# 11-SoC_POWER1.net
KiCad netlist of a schematic drawn in Altium Designer
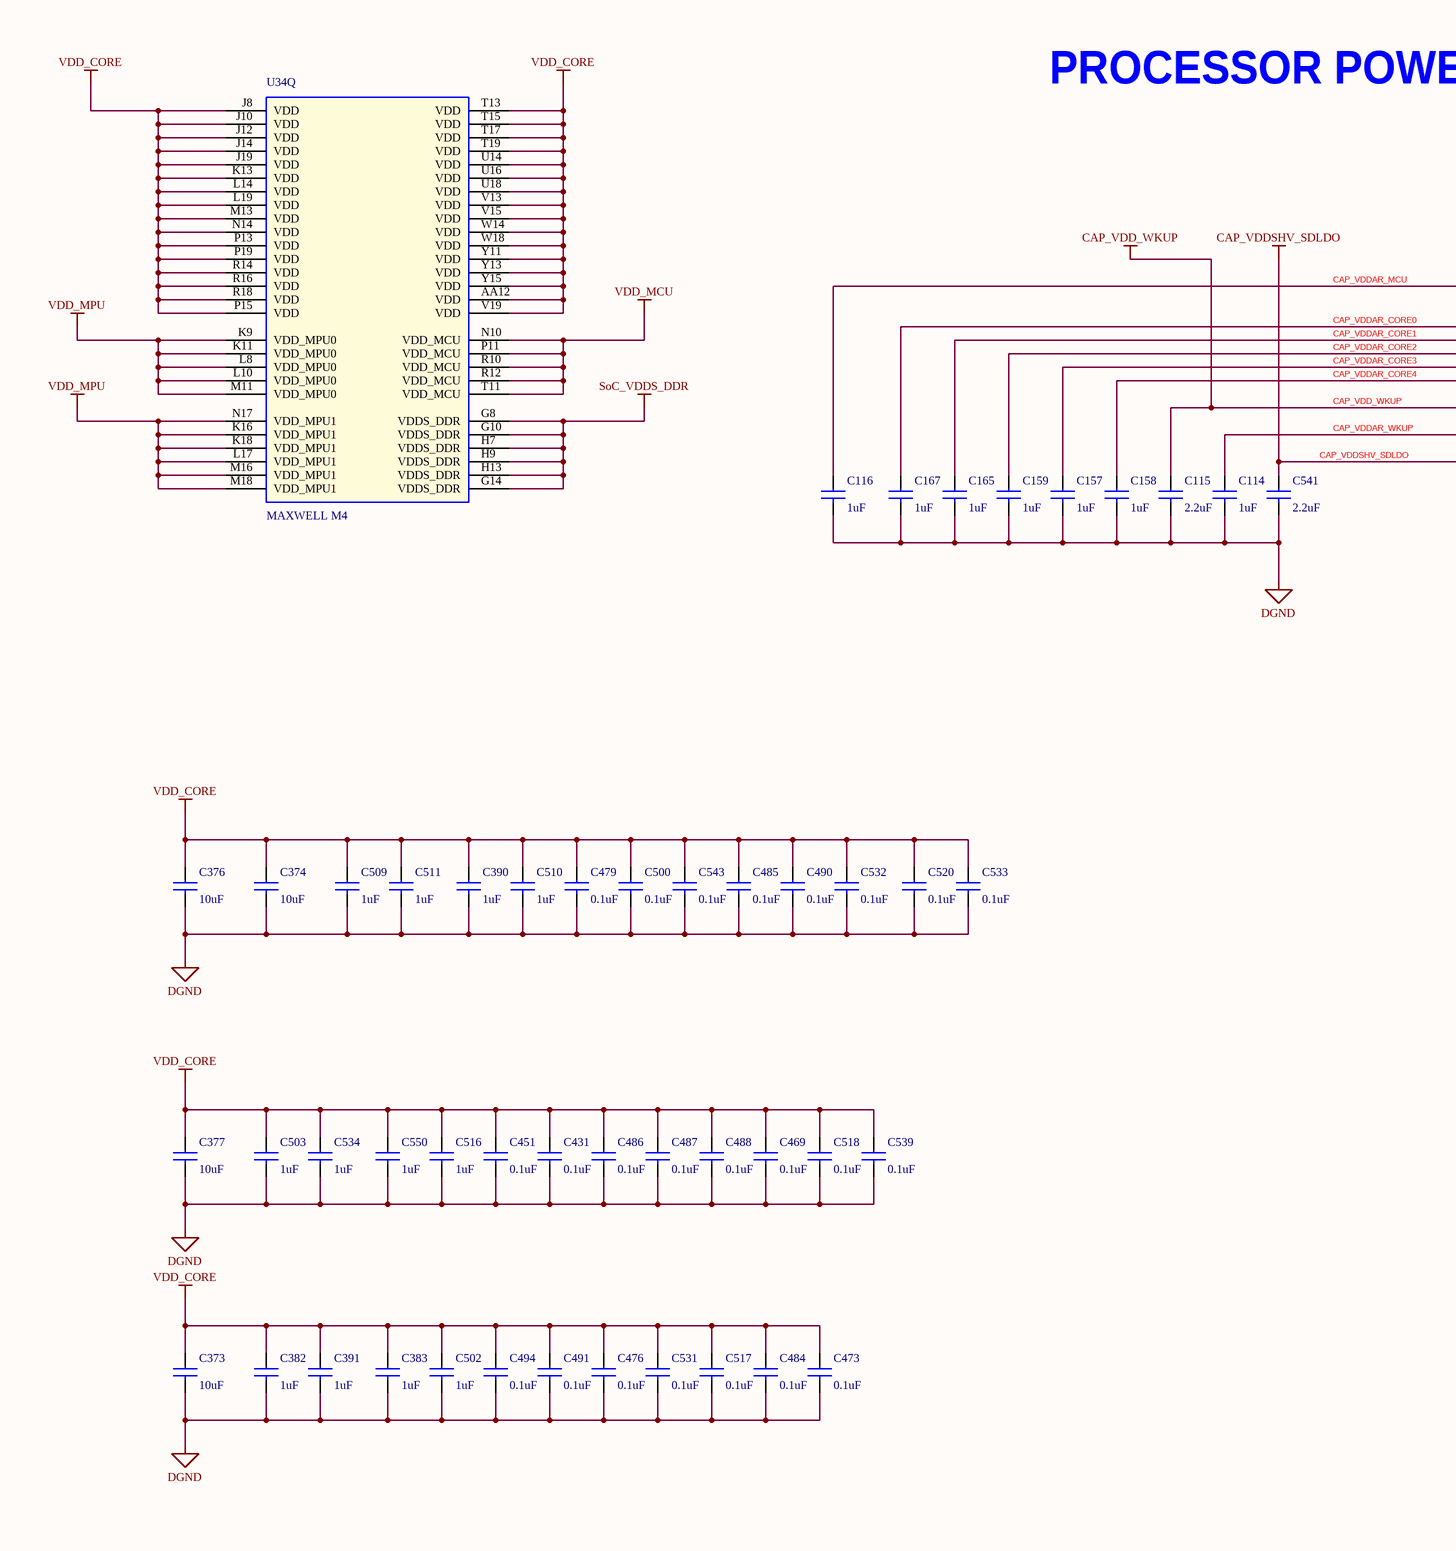
[diagram p0: 11-SoC POWER1.SchDoc, left]
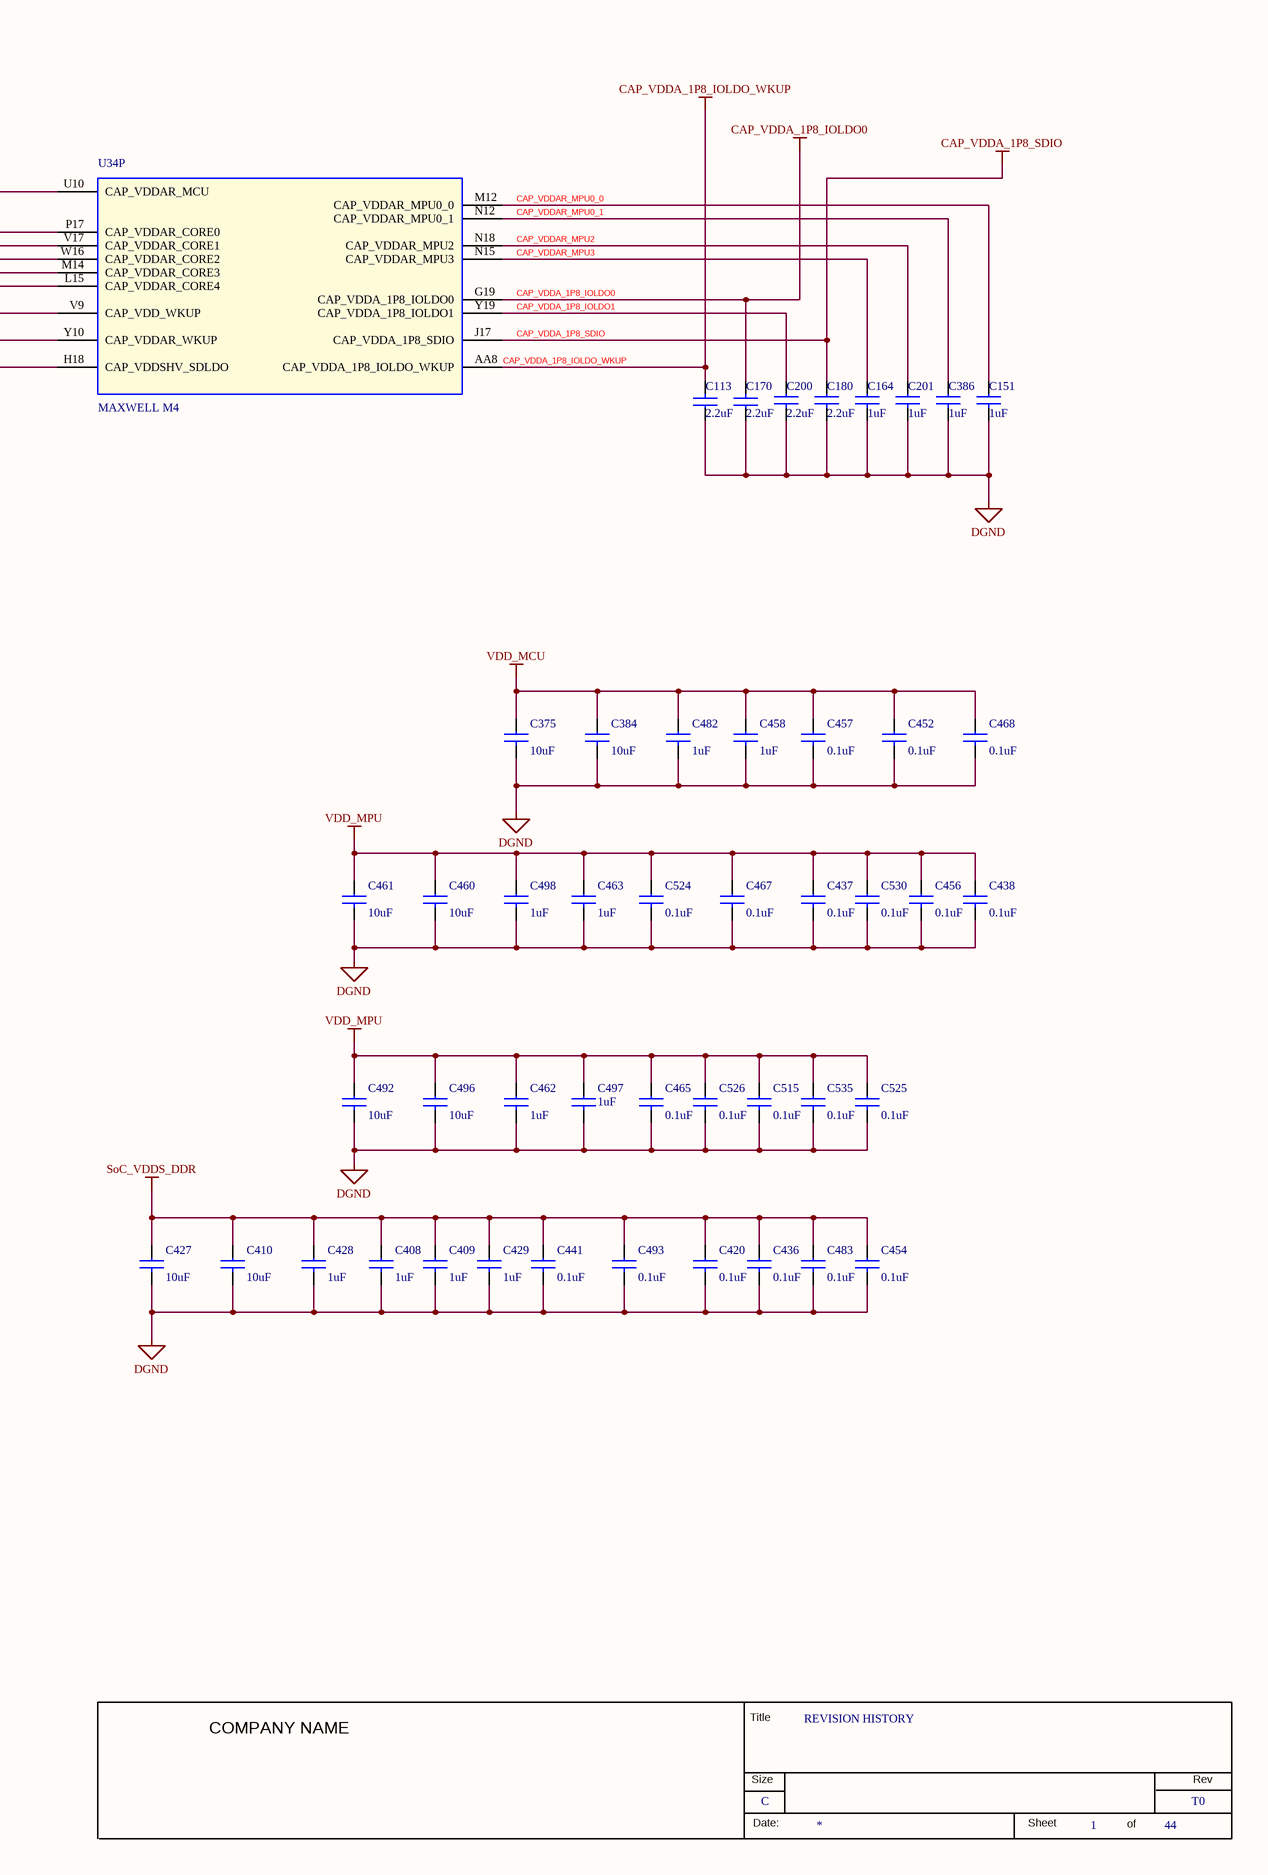
[diagram p1: 11-SoC POWER1.SchDoc, right]

(export (version "E")
  (design (tool "Eeschema 10.0.6"))
  (components
    (comp (ref "C113")
      (value "2.2uF")
      (footprint "CAP0603")
      (description "CAP CERAMIC 2.2uF 10V 10% X5R 0603")
      (fields
        (field (name "MISTRAL PART NO") "120009030289-R")
        (field (name "MFR_PART_NUMBER") "C0603C225K8PACTU")
      )
      (libsource (lib "*") (part "CAP_Dup5"))
    )
    (comp (ref "C114")
      (value "1uF")
      (footprint "CAP0402_0-75")
      (description "CAP CERAMIC 1uF 16V 20% X5R 0402")
      (fields (field (name "DISTRIBUTOR_PART_NUMBER") "587-5514-1-ND") (field (name "VOLTAGE") "16V"))
      (libsource (lib "*") (part "CAP_Dup5"))
    )
    (comp (ref "C115")
      (value "2.2uF")
      (footprint "CAP0402_0-75")
      (description "CAP CERAMIC 2.2uF 10V 20% X5R 0402")
      (fields
        (field (name "MISTRAL PART NO") "120018010016-R")
        (field (name "MFR_PART_NUMBER") "GRT155R61A225ME01D")
      )
      (libsource (lib "*") (part "CAP_Dup5"))
    )
    (comp (ref "C116")
      (value "1uF")
      (footprint "CAP0402_0-75")
      (description "CAP CERAMIC 1uF 16V 20% X5R 0402")
      (fields
        (field (name "MISTRAL PART NO") "120018020006-R")
        (field (name "MFR_PART_NUMBER") "EMK105BJ105MV-F")
      )
      (libsource (lib "*") (part "CAP_Dup5"))
    )
    (comp (ref "C151")
      (value "1uF")
      (footprint "CAP0402_0-75")
      (description "CAP CERAMIC 1uF 16V 20% X5R 0402")
      (fields (field (name "DISTRIBUTOR_PART_NUMBER") "587-5514-1-ND") (field (name "VOLTAGE") "16V"))
      (libsource (lib "*") (part "CAP_Dup5"))
    )
    (comp (ref "C157")
      (value "1uF")
      (footprint "CAP0402_0-75")
      (description "CAP CERAMIC 1uF 16V 20% X5R 0402")
      (fields (field (name "DISTRIBUTOR_PART_NUMBER") "587-5514-1-ND") (field (name "VOLTAGE") "16V"))
      (libsource (lib "*") (part "CAP_Dup5"))
    )
    (comp (ref "C158")
      (value "1uF")
      (footprint "CAP0402_0-75")
      (description "CAP CERAMIC 1uF 16V 20% X5R 0402")
      (fields
        (field (name "MISTRAL PART NO") "120018020006-R")
        (field (name "MFR_PART_NUMBER") "EMK105BJ105MV-F")
      )
      (libsource (lib "*") (part "CAP_Dup5"))
    )
    (comp (ref "C159")
      (value "1uF")
      (footprint "CAP0402_0-75")
      (description "CAP CERAMIC 1uF 16V 20% X5R 0402")
      (fields (field (name "DISTRIBUTOR_PART_NUMBER") "587-5514-1-ND") (field (name "VOLTAGE") "16V"))
      (libsource (lib "*") (part "CAP_Dup5"))
    )
    (comp (ref "C164")
      (value "1uF")
      (footprint "CAP0402_0-75")
      (description "CAP CERAMIC 1uF 16V 20% X5R 0402")
      (fields (field (name "DISTRIBUTOR_PART_NUMBER") "587-5514-1-ND") (field (name "VOLTAGE") "16V"))
      (libsource (lib "*") (part "CAP_Dup5"))
    )
    (comp (ref "C165")
      (value "1uF")
      (footprint "CAP0402_0-75")
      (description "CAP CERAMIC 1uF 16V 20% X5R 0402")
      (fields (field (name "DISTRIBUTOR_PART_NUMBER") "587-5514-1-ND") (field (name "VOLTAGE") "16V"))
      (libsource (lib "*") (part "CAP_Dup5"))
    )
    (comp (ref "C167")
      (value "1uF")
      (footprint "CAP0402_0-75")
      (description "CAP CERAMIC 1uF 16V 20% X5R 0402")
      (fields
        (field (name "MISTRAL PART NO") "120018020006-R")
        (field (name "MFR_PART_NUMBER") "EMK105BJ105MV-F")
      )
      (libsource (lib "*") (part "CAP_Dup5"))
    )
    (comp (ref "C170")
      (value "2.2uF")
      (footprint "CAP0603")
      (description "CAP CERAMIC 2.2uF 10V 10% X5R 0603")
      (fields
        (field (name "MISTRAL PART NO") "120009030289-R")
        (field (name "MFR_PART_NUMBER") "C0603C225K8PACTU")
      )
      (libsource (lib "*") (part "CAP_Dup5"))
    )
    (comp (ref "C180")
      (value "2.2uF")
      (footprint "CAP0402_0-75")
      (description "CAP CERAMIC 2.2uF 10V 20% X5R 0402")
      (fields
        (field (name "MISTRAL PART NO") "120018010016-R")
        (field (name "MFR_PART_NUMBER") "GRT155R61A225ME01D")
      )
      (libsource (lib "*") (part "CAP_Dup5"))
    )
    (comp (ref "C200")
      (value "2.2uF")
      (footprint "CAP0402_0-75")
      (description "CAP CERAMIC 2.2uF 10V 20% X5R 0402")
      (fields
        (field (name "MISTRAL PART NO") "120018010016-R")
        (field (name "MFR_PART_NUMBER") "GRT155R61A225ME01D")
      )
      (libsource (lib "*") (part "CAP_Dup5"))
    )
    (comp (ref "C201")
      (value "1uF")
      (footprint "CAP0402_0-75")
      (description "CAP CERAMIC 1uF 16V 20% X5R 0402")
      (fields
        (field (name "MISTRAL PART NO") "120018020006-R")
        (field (name "MFR_PART_NUMBER") "EMK105BJ105MV-F")
      )
      (libsource (lib "*") (part "CAP_Dup5"))
    )
    (comp (ref "C373")
      (value "10uF")
      (footprint "CAP0603_1")
      (description "CAP CERAMIC 10uF 10V 10% X5R 0603")
      (fields (field (name "DISTRIBUTOR_PART_NUMBER") "478-10766-1-ND") (field (name "VOLTAGE") "10V"))
      (libsource (lib "*") (part "CAP_Dup5"))
    )
    (comp (ref "C374")
      (value "10uF")
      (footprint "CAP0603_1")
      (description "CAP CERAMIC 10uF 10V 10% X5R 0603")
      (fields (field (name "DISTRIBUTOR_PART_NUMBER") "478-10766-1-ND") (field (name "VOLTAGE") "10V"))
      (libsource (lib "*") (part "CAP_Dup5"))
    )
    (comp (ref "C375")
      (value "10uF")
      (footprint "CAP0603_1")
      (description "CAP CERAMIC 10uF 10V 10% X5R 0603")
      (fields
        (field (name "MISTRAL PART NO") "120010080001-R")
        (field (name "MFR_PART_NUMBER") "0603ZD106KAT2A")
      )
      (libsource (lib "*") (part "CAP_Dup5"))
    )
    (comp (ref "C376")
      (value "10uF")
      (footprint "CAP0603_1")
      (description "CAP CERAMIC 10uF 10V 10% X5R 0603")
      (fields (field (name "DISTRIBUTOR_PART_NUMBER") "478-10766-1-ND") (field (name "VOLTAGE") "10V"))
      (libsource (lib "*") (part "CAP_Dup5"))
    )
    (comp (ref "C377")
      (value "10uF")
      (footprint "CAP0603_1")
      (description "CAP CERAMIC 10uF 10V 10% X5R 0603")
      (fields
        (field (name "MISTRAL PART NO") "120010080001-R")
        (field (name "MFR_PART_NUMBER") "0603ZD106KAT2A")
      )
      (libsource (lib "*") (part "CAP_Dup5"))
    )
    (comp (ref "C382")
      (value "1uF")
      (footprint "CAP0402_0-75")
      (description "CAP CERAMIC 1uF 16V 20% X5R 0402")
      (fields (field (name "DISTRIBUTOR_PART_NUMBER") "587-5514-1-ND") (field (name "VOLTAGE") "16V"))
      (libsource (lib "*") (part "CAP_Dup5"))
    )
    (comp (ref "C383")
      (value "1uF")
      (footprint "CAP0402_0-75")
      (description "CAP CERAMIC 1uF 16V 20% X5R 0402")
      (fields (field (name "DISTRIBUTOR_PART_NUMBER") "587-5514-1-ND") (field (name "VOLTAGE") "16V"))
      (libsource (lib "*") (part "CAP_Dup5"))
    )
    (comp (ref "C384")
      (value "10uF")
      (footprint "CAP0603_1")
      (description "CAP CERAMIC 10uF 10V 10% X5R 0603")
      (fields
        (field (name "MISTRAL PART NO") "120010080001-R")
        (field (name "MFR_PART_NUMBER") "0603ZD106KAT2A")
      )
      (libsource (lib "*") (part "CAP_Dup5"))
    )
    (comp (ref "C386")
      (value "1uF")
      (footprint "CAP0402_0-75")
      (description "CAP CERAMIC 1uF 16V 20% X5R 0402")
      (fields (field (name "DISTRIBUTOR_PART_NUMBER") "587-5514-1-ND") (field (name "VOLTAGE") "16V"))
      (libsource (lib "*") (part "CAP_Dup5"))
    )
    (comp (ref "C390")
      (value "1uF")
      (footprint "CAP0402_0-75")
      (description "CAP CERAMIC 1uF 16V 20% X5R 0402")
      (fields (field (name "DISTRIBUTOR_PART_NUMBER") "587-5514-1-ND") (field (name "VOLTAGE") "16V"))
      (libsource (lib "*") (part "CAP_Dup5"))
    )
    (comp (ref "C391")
      (value "1uF")
      (footprint "CAP0402_0-75")
      (description "CAP CERAMIC 1uF 16V 20% X5R 0402")
      (fields (field (name "DISTRIBUTOR_PART_NUMBER") "587-5514-1-ND") (field (name "VOLTAGE") "16V"))
      (libsource (lib "*") (part "CAP_Dup5"))
    )
    (comp (ref "C408")
      (value "1uF")
      (footprint "CAP0402_0-75")
      (description "CAP CERAMIC 1uF 16V 20% X5R 0402")
      (fields (field (name "DISTRIBUTOR_PART_NUMBER") "587-5514-1-ND") (field (name "VOLTAGE") "16V"))
      (libsource (lib "*") (part "CAP_Dup5"))
    )
    (comp (ref "C409")
      (value "1uF")
      (footprint "CAP0402_0-75")
      (description "CAP CERAMIC 1uF 16V 20% X5R 0402")
      (fields (field (name "DISTRIBUTOR_PART_NUMBER") "587-5514-1-ND") (field (name "VOLTAGE") "16V"))
      (libsource (lib "*") (part "CAP_Dup5"))
    )
    (comp (ref "C410")
      (value "10uF")
      (footprint "CAP0603_1")
      (description "CAP CERAMIC 10uF 10V 10% X5R 0603")
      (fields
        (field (name "MISTRAL PART NO") "120010080001-R")
        (field (name "MFR_PART_NUMBER") "0603ZD106KAT2A")
      )
      (libsource (lib "*") (part "CAP_Dup5"))
    )
    (comp (ref "C420")
      (value "0.1uF")
      (footprint "CAP0201_0-5")
      (description "CAP CERAMIC 0.1uF 16V 10% X5R 0201")
      (fields
        (field (name "MISTRAL PART NO") "120009030072-R")
        (field (name "MFR_PART_NUMBER") "GRM033R61C104KE84J")
      )
      (libsource (lib "*") (part "CAP_Dup5"))
    )
    (comp (ref "C427")
      (value "10uF")
      (footprint "CAP0603_1")
      (description "CAP CERAMIC 10uF 10V 10% X5R 0603")
      (fields
        (field (name "MISTRAL PART NO") "120010080001-R")
        (field (name "MFR_PART_NUMBER") "0603ZD106KAT2A")
      )
      (libsource (lib "*") (part "CAP_Dup5"))
    )
    (comp (ref "C428")
      (value "1uF")
      (footprint "CAP0402_0-75")
      (description "CAP CERAMIC 1uF 16V 20% X5R 0402")
      (fields
        (field (name "MISTRAL PART NO") "120018020006-R")
        (field (name "MFR_PART_NUMBER") "EMK105BJ105MV-F")
      )
      (libsource (lib "*") (part "CAP_Dup5"))
    )
    (comp (ref "C429")
      (value "1uF")
      (footprint "CAP0402_0-75")
      (description "CAP CERAMIC 1uF 16V 20% X5R 0402")
      (fields
        (field (name "MISTRAL PART NO") "120018020006-R")
        (field (name "MFR_PART_NUMBER") "EMK105BJ105MV-F")
      )
      (libsource (lib "*") (part "CAP_Dup5"))
    )
    (comp (ref "C431")
      (value "0.1uF")
      (footprint "CAP0201_0-5")
      (description "CAP CERAMIC 0.1uF 16V 10% X5R 0201")
      (fields (field (name "DISTRIBUTOR_PART_NUMBER") "490-16742-1-ND") (field (name "VOLTAGE") "16V"))
      (libsource (lib "*") (part "CAP_Dup5"))
    )
    (comp (ref "C436")
      (value "0.1uF")
      (footprint "CAP0201_0-5")
      (description "CAP CERAMIC 0.1uF 16V 10% X5R 0201")
      (fields (field (name "DISTRIBUTOR_PART_NUMBER") "490-16742-1-ND") (field (name "VOLTAGE") "16V"))
      (libsource (lib "*") (part "CAP_Dup5"))
    )
    (comp (ref "C437")
      (value "0.1uF")
      (footprint "CAP0201_0-5")
      (description "CAP CERAMIC 0.1uF 16V 10% X5R 0201")
      (fields
        (field (name "MISTRAL PART NO") "120009030072-R")
        (field (name "MFR_PART_NUMBER") "GRM033R61C104KE84J")
      )
      (libsource (lib "*") (part "CAP_Dup5"))
    )
    (comp (ref "C438")
      (value "0.1uF")
      (footprint "CAP0201_0-5")
      (description "CAP CERAMIC 0.1uF 16V 10% X5R 0201")
      (fields (field (name "DISTRIBUTOR_PART_NUMBER") "490-16742-1-ND") (field (name "VOLTAGE") "16V"))
      (libsource (lib "*") (part "CAP_Dup5"))
    )
    (comp (ref "C441")
      (value "0.1uF")
      (footprint "CAP0201_0-5")
      (description "CAP CERAMIC 0.1uF 16V 10% X5R 0201")
      (fields
        (field (name "MISTRAL PART NO") "120009030072-R")
        (field (name "MFR_PART_NUMBER") "GRM033R61C104KE84J")
      )
      (libsource (lib "*") (part "CAP_Dup5"))
    )
    (comp (ref "C451")
      (value "0.1uF")
      (footprint "CAP0201_0-5")
      (description "CAP CERAMIC 0.1uF 16V 10% X5R 0201")
      (fields (field (name "DISTRIBUTOR_PART_NUMBER") "490-16742-1-ND") (field (name "VOLTAGE") "16V"))
      (libsource (lib "*") (part "CAP_Dup5"))
    )
    (comp (ref "C452")
      (value "0.1uF")
      (footprint "CAP0201_0-5")
      (description "CAP CERAMIC 0.1uF 16V 10% X5R 0201")
      (fields
        (field (name "MISTRAL PART NO") "120009030072-R")
        (field (name "MFR_PART_NUMBER") "GRM033R61C104KE84J")
      )
      (libsource (lib "*") (part "CAP_Dup5"))
    )
    (comp (ref "C454")
      (value "0.1uF")
      (footprint "CAP0201_0-5")
      (description "CAP CERAMIC 0.1uF 16V 10% X5R 0201")
      (fields
        (field (name "MISTRAL PART NO") "120009030072-R")
        (field (name "MFR_PART_NUMBER") "GRM033R61C104KE84J")
      )
      (libsource (lib "*") (part "CAP_Dup5"))
    )
    (comp (ref "C456")
      (value "0.1uF")
      (footprint "CAP0201_0-5")
      (description "CAP CERAMIC 0.1uF 16V 10% X5R 0201")
      (fields
        (field (name "MISTRAL PART NO") "120009030072-R")
        (field (name "MFR_PART_NUMBER") "GRM033R61C104KE84J")
      )
      (libsource (lib "*") (part "CAP_Dup5"))
    )
    (comp (ref "C457")
      (value "0.1uF")
      (footprint "CAP0201_0-5")
      (description "CAP CERAMIC 0.1uF 16V 10% X5R 0201")
      (fields (field (name "DISTRIBUTOR_PART_NUMBER") "490-16742-1-ND") (field (name "VOLTAGE") "16V"))
      (libsource (lib "*") (part "CAP_Dup5"))
    )
    (comp (ref "C458")
      (value "1uF")
      (footprint "CAP0402_0-75")
      (description "CAP CERAMIC 1uF 16V 20% X5R 0402")
      (fields (field (name "DISTRIBUTOR_PART_NUMBER") "587-5514-1-ND") (field (name "VOLTAGE") "16V"))
      (libsource (lib "*") (part "CAP_Dup5"))
    )
    (comp (ref "C460")
      (value "10uF")
      (footprint "CAP0603_1")
      (description "CAP CERAMIC 10uF 10V 10% X5R 0603")
      (fields (field (name "DISTRIBUTOR_PART_NUMBER") "478-10766-1-ND") (field (name "VOLTAGE") "10V"))
      (libsource (lib "*") (part "CAP_Dup5"))
    )
    (comp (ref "C461")
      (value "10uF")
      (footprint "CAP0603_1")
      (description "CAP CERAMIC 10uF 10V 10% X5R 0603")
      (fields (field (name "DISTRIBUTOR_PART_NUMBER") "478-10766-1-ND") (field (name "VOLTAGE") "10V"))
      (libsource (lib "*") (part "CAP_Dup5"))
    )
    (comp (ref "C462")
      (value "1uF")
      (footprint "CAP0402_0-75")
      (description "CAP CERAMIC 1uF 16V 20% X5R 0402")
      (fields
        (field (name "MISTRAL PART NO") "120018020006-R")
        (field (name "MFR_PART_NUMBER") "EMK105BJ105MV-F")
      )
      (libsource (lib "*") (part "CAP_Dup5"))
    )
    (comp (ref "C463")
      (value "1uF")
      (footprint "CAP0402_0-75")
      (description "CAP CERAMIC 1uF 16V 20% X5R 0402")
      (fields
        (field (name "MISTRAL PART NO") "120018020006-R")
        (field (name "MFR_PART_NUMBER") "EMK105BJ105MV-F")
      )
      (libsource (lib "*") (part "CAP_Dup5"))
    )
    (comp (ref "C465")
      (value "0.1uF")
      (footprint "CAP0201_0-5")
      (description "CAP CERAMIC 0.1uF 16V 10% X5R 0201")
      (fields
        (field (name "MISTRAL PART NO") "120009030072-R")
        (field (name "MFR_PART_NUMBER") "GRM033R61C104KE84J")
      )
      (libsource (lib "*") (part "CAP_Dup5"))
    )
    (comp (ref "C467")
      (value "0.1uF")
      (footprint "CAP0201_0-5")
      (description "CAP CERAMIC 0.1uF 16V 10% X5R 0201")
      (fields (field (name "DISTRIBUTOR_PART_NUMBER") "490-16742-1-ND") (field (name "VOLTAGE") "16V"))
      (libsource (lib "*") (part "CAP_Dup5"))
    )
    (comp (ref "C468")
      (value "0.1uF")
      (footprint "CAP0201_0-5")
      (description "CAP CERAMIC 0.1uF 16V 10% X5R 0201")
      (fields (field (name "DISTRIBUTOR_PART_NUMBER") "490-16742-1-ND") (field (name "VOLTAGE") "16V"))
      (libsource (lib "*") (part "CAP_Dup5"))
    )
    (comp (ref "C469")
      (value "0.1uF")
      (footprint "CAP0201_0-5")
      (description "CAP CERAMIC 0.1uF 16V 10% X5R 0201")
      (fields (field (name "DISTRIBUTOR_PART_NUMBER") "490-16742-1-ND") (field (name "VOLTAGE") "16V"))
      (libsource (lib "*") (part "CAP_Dup5"))
    )
    (comp (ref "C473")
      (value "0.1uF")
      (footprint "CAP0201_0-5")
      (description "CAP CERAMIC 0.1uF 16V 10% X5R 0201")
      (fields
        (field (name "MISTRAL PART NO") "120009030072-R")
        (field (name "MFR_PART_NUMBER") "GRM033R61C104KE84J")
      )
      (libsource (lib "*") (part "CAP_Dup5"))
    )
    (comp (ref "C476")
      (value "0.1uF")
      (footprint "CAP0201_0-5")
      (description "CAP CERAMIC 0.1uF 16V 10% X5R 0201")
      (fields (field (name "DISTRIBUTOR_PART_NUMBER") "490-16742-1-ND") (field (name "VOLTAGE") "16V"))
      (libsource (lib "*") (part "CAP_Dup5"))
    )
    (comp (ref "C479")
      (value "0.1uF")
      (footprint "CAP0201_0-5")
      (description "CAP CERAMIC 0.1uF 16V 10% X5R 0201")
      (fields (field (name "DISTRIBUTOR_PART_NUMBER") "490-16742-1-ND") (field (name "VOLTAGE") "16V"))
      (libsource (lib "*") (part "CAP_Dup5"))
    )
    (comp (ref "C482")
      (value "1uF")
      (footprint "CAP0402_0-75")
      (description "CAP CERAMIC 1uF 16V 20% X5R 0402")
      (fields
        (field (name "MISTRAL PART NO") "120018020006-R")
        (field (name "MFR_PART_NUMBER") "EMK105BJ105MV-F")
      )
      (libsource (lib "*") (part "CAP_Dup5"))
    )
    (comp (ref "C483")
      (value "0.1uF")
      (footprint "CAP0201_0-5")
      (description "CAP CERAMIC 0.1uF 16V 10% X5R 0201")
      (fields (field (name "DISTRIBUTOR_PART_NUMBER") "490-16742-1-ND") (field (name "VOLTAGE") "16V"))
      (libsource (lib "*") (part "CAP_Dup5"))
    )
    (comp (ref "C484")
      (value "0.1uF")
      (footprint "CAP0201_0-5")
      (description "CAP CERAMIC 0.1uF 16V 10% X5R 0201")
      (fields (field (name "DISTRIBUTOR_PART_NUMBER") "490-16742-1-ND") (field (name "VOLTAGE") "16V"))
      (libsource (lib "*") (part "CAP_Dup5"))
    )
    (comp (ref "C485")
      (value "0.1uF")
      (footprint "CAP0201_0-5")
      (description "CAP CERAMIC 0.1uF 16V 10% X5R 0201")
      (fields (field (name "DISTRIBUTOR_PART_NUMBER") "490-16742-1-ND") (field (name "VOLTAGE") "16V"))
      (libsource (lib "*") (part "CAP_Dup5"))
    )
    (comp (ref "C486")
      (value "0.1uF")
      (footprint "CAP0201_0-5")
      (description "CAP CERAMIC 0.1uF 16V 10% X5R 0201")
      (fields
        (field (name "MISTRAL PART NO") "120009030072-R")
        (field (name "MFR_PART_NUMBER") "GRM033R61C104KE84J")
      )
      (libsource (lib "*") (part "CAP_Dup5"))
    )
    (comp (ref "C487")
      (value "0.1uF")
      (footprint "CAP0201_0-5")
      (description "CAP CERAMIC 0.1uF 16V 10% X5R 0201")
      (fields
        (field (name "MISTRAL PART NO") "120009030072-R")
        (field (name "MFR_PART_NUMBER") "GRM033R61C104KE84J")
      )
      (libsource (lib "*") (part "CAP_Dup5"))
    )
    (comp (ref "C488")
      (value "0.1uF")
      (footprint "CAP0201_0-5")
      (description "CAP CERAMIC 0.1uF 16V 10% X5R 0201")
      (fields
        (field (name "MISTRAL PART NO") "120009030072-R")
        (field (name "MFR_PART_NUMBER") "GRM033R61C104KE84J")
      )
      (libsource (lib "*") (part "CAP_Dup5"))
    )
    (comp (ref "C490")
      (value "0.1uF")
      (footprint "CAP0201_0-5")
      (description "CAP CERAMIC 0.1uF 16V 10% X5R 0201")
      (fields
        (field (name "MISTRAL PART NO") "120009030072-R")
        (field (name "MFR_PART_NUMBER") "GRM033R61C104KE84J")
      )
      (libsource (lib "*") (part "CAP_Dup5"))
    )
    (comp (ref "C491")
      (value "0.1uF")
      (footprint "CAP0201_0-5")
      (description "CAP CERAMIC 0.1uF 16V 10% X5R 0201")
      (fields (field (name "DISTRIBUTOR_PART_NUMBER") "490-16742-1-ND") (field (name "VOLTAGE") "16V"))
      (libsource (lib "*") (part "CAP_Dup5"))
    )
    (comp (ref "C492")
      (value "10uF")
      (footprint "CAP0603_1")
      (description "CAP CERAMIC 10uF 10V 10% X5R 0603")
      (fields (field (name "DISTRIBUTOR_PART_NUMBER") "478-10766-1-ND") (field (name "VOLTAGE") "10V"))
      (libsource (lib "*") (part "CAP_Dup5"))
    )
    (comp (ref "C493")
      (value "0.1uF")
      (footprint "CAP0201_0-5")
      (description "CAP CERAMIC 0.1uF 16V 10% X5R 0201")
      (fields (field (name "DISTRIBUTOR_PART_NUMBER") "490-16742-1-ND") (field (name "VOLTAGE") "16V"))
      (libsource (lib "*") (part "CAP_Dup5"))
    )
    (comp (ref "C494")
      (value "0.1uF")
      (footprint "CAP0201_0-5")
      (description "CAP CERAMIC 0.1uF 16V 10% X5R 0201")
      (fields
        (field (name "MISTRAL PART NO") "120009030072-R")
        (field (name "MFR_PART_NUMBER") "GRM033R61C104KE84J")
      )
      (libsource (lib "*") (part "CAP_Dup5"))
    )
    (comp (ref "C496")
      (value "10uF")
      (footprint "CAP0603_1")
      (description "CAP CERAMIC 10uF 10V 10% X5R 0603")
      (fields (field (name "DISTRIBUTOR_PART_NUMBER") "478-10766-1-ND") (field (name "VOLTAGE") "10V"))
      (libsource (lib "*") (part "CAP_Dup5"))
    )
    (comp (ref "C497")
      (value "1uF")
      (footprint "CAP0402_0-75")
      (description "CAP CERAMIC 1uF 16V 20% X5R 0402")
      (fields (field (name "DISTRIBUTOR_PART_NUMBER") "587-5514-1-ND") (field (name "VOLTAGE") "16V"))
      (libsource (lib "*") (part "CAP_Dup5"))
    )
    (comp (ref "C498")
      (value "1uF")
      (footprint "CAP0402_0-75")
      (description "CAP CERAMIC 1uF 16V 20% X5R 0402")
      (fields
        (field (name "MISTRAL PART NO") "120018020006-R")
        (field (name "MFR_PART_NUMBER") "EMK105BJ105MV-F")
      )
      (libsource (lib "*") (part "CAP_Dup5"))
    )
    (comp (ref "C500")
      (value "0.1uF")
      (footprint "CAP0201_0-5")
      (description "CAP CERAMIC 0.1uF 16V 10% X5R 0201")
      (fields (field (name "DISTRIBUTOR_PART_NUMBER") "490-16742-1-ND") (field (name "VOLTAGE") "16V"))
      (libsource (lib "*") (part "CAP_Dup5"))
    )
    (comp (ref "C502")
      (value "1uF")
      (footprint "CAP0402_0-75")
      (description "CAP CERAMIC 1uF 16V 20% X5R 0402")
      (fields (field (name "DISTRIBUTOR_PART_NUMBER") "587-5514-1-ND") (field (name "VOLTAGE") "16V"))
      (libsource (lib "*") (part "CAP_Dup5"))
    )
    (comp (ref "C503")
      (value "1uF")
      (footprint "CAP0402_0-75")
      (description "CAP CERAMIC 1uF 16V 20% X5R 0402")
      (fields
        (field (name "MISTRAL PART NO") "120018020006-R")
        (field (name "MFR_PART_NUMBER") "EMK105BJ105MV-F")
      )
      (libsource (lib "*") (part "CAP_Dup5"))
    )
    (comp (ref "C509")
      (value "1uF")
      (footprint "CAP0402_0-75")
      (description "CAP CERAMIC 1uF 16V 20% X5R 0402")
      (fields (field (name "DISTRIBUTOR_PART_NUMBER") "587-5514-1-ND") (field (name "VOLTAGE") "16V"))
      (libsource (lib "*") (part "CAP_Dup5"))
    )
    (comp (ref "C510")
      (value "1uF")
      (footprint "CAP0402_0-75")
      (description "CAP CERAMIC 1uF 16V 20% X5R 0402")
      (fields (field (name "DISTRIBUTOR_PART_NUMBER") "587-5514-1-ND") (field (name "VOLTAGE") "16V"))
      (libsource (lib "*") (part "CAP_Dup5"))
    )
    (comp (ref "C511")
      (value "1uF")
      (footprint "CAP0402_0-75")
      (description "CAP CERAMIC 1uF 16V 20% X5R 0402")
      (fields
        (field (name "MISTRAL PART NO") "120018020006-R")
        (field (name "MFR_PART_NUMBER") "EMK105BJ105MV-F")
      )
      (libsource (lib "*") (part "CAP_Dup5"))
    )
    (comp (ref "C515")
      (value "0.1uF")
      (footprint "CAP0201_0-5")
      (description "CAP CERAMIC 0.1uF 16V 10% X5R 0201")
      (fields (field (name "DISTRIBUTOR_PART_NUMBER") "490-16742-1-ND") (field (name "VOLTAGE") "16V"))
      (libsource (lib "*") (part "CAP_Dup5"))
    )
    (comp (ref "C516")
      (value "1uF")
      (footprint "CAP0402_0-75")
      (description "CAP CERAMIC 1uF 16V 20% X5R 0402")
      (fields
        (field (name "MISTRAL PART NO") "120018020006-R")
        (field (name "MFR_PART_NUMBER") "EMK105BJ105MV-F")
      )
      (libsource (lib "*") (part "CAP_Dup5"))
    )
    (comp (ref "C517")
      (value "0.1uF")
      (footprint "CAP0201_0-5")
      (description "CAP CERAMIC 0.1uF 16V 10% X5R 0201")
      (fields
        (field (name "MISTRAL PART NO") "120009030072-R")
        (field (name "MFR_PART_NUMBER") "GRM033R61C104KE84J")
      )
      (libsource (lib "*") (part "CAP_Dup5"))
    )
    (comp (ref "C518")
      (value "0.1uF")
      (footprint "CAP0201_0-5")
      (description "CAP CERAMIC 0.1uF 16V 10% X5R 0201")
      (fields
        (field (name "MISTRAL PART NO") "120009030072-R")
        (field (name "MFR_PART_NUMBER") "GRM033R61C104KE84J")
      )
      (libsource (lib "*") (part "CAP_Dup5"))
    )
    (comp (ref "C520")
      (value "0.1uF")
      (footprint "CAP0201_0-5")
      (description "CAP CERAMIC 0.1uF 16V 10% X5R 0201")
      (fields
        (field (name "MISTRAL PART NO") "120009030072-R")
        (field (name "MFR_PART_NUMBER") "GRM033R61C104KE84J")
      )
      (libsource (lib "*") (part "CAP_Dup5"))
    )
    (comp (ref "C524")
      (value "0.1uF")
      (footprint "CAP0201_0-5")
      (description "CAP CERAMIC 0.1uF 16V 10% X5R 0201")
      (fields
        (field (name "MISTRAL PART NO") "120009030072-R")
        (field (name "MFR_PART_NUMBER") "GRM033R61C104KE84J")
      )
      (libsource (lib "*") (part "CAP_Dup5"))
    )
    (comp (ref "C525")
      (value "0.1uF")
      (footprint "CAP0201_0-5")
      (description "CAP CERAMIC 0.1uF 16V 10% X5R 0201")
      (fields (field (name "DISTRIBUTOR_PART_NUMBER") "490-16742-1-ND") (field (name "VOLTAGE") "16V"))
      (libsource (lib "*") (part "CAP_Dup5"))
    )
    (comp (ref "C526")
      (value "0.1uF")
      (footprint "CAP0201_0-5")
      (description "CAP CERAMIC 0.1uF 16V 10% X5R 0201")
      (fields
        (field (name "MISTRAL PART NO") "120009030072-R")
        (field (name "MFR_PART_NUMBER") "GRM033R61C104KE84J")
      )
      (libsource (lib "*") (part "CAP_Dup5"))
    )
    (comp (ref "C530")
      (value "0.1uF")
      (footprint "CAP0201_0-5")
      (description "CAP CERAMIC 0.1uF 16V 10% X5R 0201")
      (fields (field (name "DISTRIBUTOR_PART_NUMBER") "490-16742-1-ND") (field (name "VOLTAGE") "16V"))
      (libsource (lib "*") (part "CAP_Dup5"))
    )
    (comp (ref "C531")
      (value "0.1uF")
      (footprint "CAP0201_0-5")
      (description "CAP CERAMIC 0.1uF 16V 10% X5R 0201")
      (fields (field (name "DISTRIBUTOR_PART_NUMBER") "490-16742-1-ND") (field (name "VOLTAGE") "16V"))
      (libsource (lib "*") (part "CAP_Dup5"))
    )
    (comp (ref "C532")
      (value "0.1uF")
      (footprint "CAP0201_0-5")
      (description "CAP CERAMIC 0.1uF 16V 10% X5R 0201")
      (fields (field (name "DISTRIBUTOR_PART_NUMBER") "490-16742-1-ND") (field (name "VOLTAGE") "16V"))
      (libsource (lib "*") (part "CAP_Dup5"))
    )
    (comp (ref "C533")
      (value "0.1uF")
      (footprint "CAP0201_0-5")
      (description "CAP CERAMIC 0.1uF 16V 10% X5R 0201")
      (fields (field (name "DISTRIBUTOR_PART_NUMBER") "490-16742-1-ND") (field (name "VOLTAGE") "16V"))
      (libsource (lib "*") (part "CAP_Dup5"))
    )
    (comp (ref "C534")
      (value "1uF")
      (footprint "CAP0402_0-75")
      (description "CAP CERAMIC 1uF 16V 20% X5R 0402")
      (fields
        (field (name "MISTRAL PART NO") "120018020006-R")
        (field (name "MFR_PART_NUMBER") "EMK105BJ105MV-F")
      )
      (libsource (lib "*") (part "CAP_Dup5"))
    )
    (comp (ref "C535")
      (value "0.1uF")
      (footprint "CAP0201_0-5")
      (description "CAP CERAMIC 0.1uF 16V 10% X5R 0201")
      (fields
        (field (name "MISTRAL PART NO") "120009030072-R")
        (field (name "MFR_PART_NUMBER") "GRM033R61C104KE84J")
      )
      (libsource (lib "*") (part "CAP_Dup5"))
    )
    (comp (ref "C539")
      (value "0.1uF")
      (footprint "CAP0201_0-5")
      (description "CAP CERAMIC 0.1uF 16V 10% X5R 0201")
      (fields (field (name "DISTRIBUTOR_PART_NUMBER") "490-16742-1-ND") (field (name "VOLTAGE") "16V"))
      (libsource (lib "*") (part "CAP_Dup5"))
    )
    (comp (ref "C541")
      (value "2.2uF")
      (footprint "CAP0402_0-75")
      (description "CAP CERAMIC 2.2uF 10V 20% X5R 0402")
      (fields
        (field (name "MISTRAL PART NO") "120018010016-R")
        (field (name "MFR_PART_NUMBER") "GRT155R61A225ME01D")
      )
      (libsource (lib "*") (part "CAP_Dup5"))
    )
    (comp (ref "C543")
      (value "0.1uF")
      (footprint "CAP0201_0-5")
      (description "CAP CERAMIC 0.1uF 16V 10% X5R 0201")
      (fields
        (field (name "MISTRAL PART NO") "120009030072-R")
        (field (name "MFR_PART_NUMBER") "GRM033R61C104KE84J")
      )
      (libsource (lib "*") (part "CAP_Dup5"))
    )
    (comp (ref "C550")
      (value "1uF")
      (footprint "CAP0402_0-75")
      (description "CAP CERAMIC 1uF 16V 20% X5R 0402")
      (fields (field (name "DISTRIBUTOR_PART_NUMBER") "587-5514-1-ND") (field (name "VOLTAGE") "16V"))
      (libsource (lib "*") (part "CAP_Dup5"))
    )
    (comp (ref "U34")
      (value "MAXWELL M4")
      (footprint "BGA784_31-49_910X910_1-7")
      (description "IC MAXWELL MICRO CONTROLLER UNIT BGA784")
      (fields
        (field (name "MISTRAL PART NO") "141217100003")
        (field (name "MFR_PART_NUMBER") "MAXWELL M4_EVM")
      )
      (libsource (lib "*") (part "AM654X_BGA784"))
    )
  )
  (nets
    (net (code "1") (name "/CAP_VDDAR_CORE0") (class "Default")
      (node (ref "C167") (pin "1") (pinfunction "1_1") (pintype "passive"))
      (node (ref "U34") (pin "P17") (pinfunction "CAP_VDDAR_CORE0_P17") (pintype "power_in"))
    )
    (net (code "2") (name "/CAP_VDDAR_CORE1") (class "Default")
      (node (ref "C165") (pin "1") (pinfunction "1_1") (pintype "passive"))
      (node (ref "U34") (pin "V17") (pinfunction "CAP_VDDAR_CORE1_V17") (pintype "power_in"))
    )
    (net (code "3") (name "/CAP_VDDAR_CORE2") (class "Default")
      (node (ref "C159") (pin "1") (pinfunction "1_1") (pintype "passive"))
      (node (ref "U34") (pin "W16") (pinfunction "CAP_VDDAR_CORE2_W16") (pintype "power_in"))
    )
    (net (code "4") (name "/CAP_VDDAR_CORE3") (class "Default")
      (node (ref "C157") (pin "1") (pinfunction "1_1") (pintype "passive"))
      (node (ref "U34") (pin "M14") (pinfunction "CAP_VDDAR_CORE3_M14") (pintype "power_in"))
    )
    (net (code "5") (name "/CAP_VDDAR_CORE4") (class "Default")
      (node (ref "C158") (pin "1") (pinfunction "1_1") (pintype "passive"))
      (node (ref "U34") (pin "L15") (pinfunction "CAP_VDDAR_CORE4_L15") (pintype "power_in"))
    )
    (net (code "6") (name "/CAP_VDDAR_MCU") (class "Default")
      (node (ref "C116") (pin "1") (pinfunction "1_1") (pintype "passive"))
      (node (ref "U34") (pin "U10") (pinfunction "CAP_VDDAR_MCU_U10") (pintype "power_in"))
    )
    (net (code "7") (name "/CAP_VDDAR_MPU0_0") (class "Default")
      (node (ref "C151") (pin "1") (pinfunction "1_1") (pintype "passive"))
      (node (ref "U34") (pin "M12") (pinfunction "CAP_VDDAR_MPU0_0_M12") (pintype "power_in"))
    )
    (net (code "8") (name "/CAP_VDDAR_MPU0_1") (class "Default")
      (node (ref "C386") (pin "1") (pinfunction "1_1") (pintype "passive"))
      (node (ref "U34") (pin "N12") (pinfunction "CAP_VDDAR_MPU0_1_N12") (pintype "power_in"))
    )
    (net (code "9") (name "/CAP_VDDAR_MPU2") (class "Default")
      (node (ref "C201") (pin "1") (pinfunction "1_1") (pintype "passive"))
      (node (ref "U34") (pin "N18") (pinfunction "CAP_VDDAR_MPU2_N18") (pintype "power_in"))
    )
    (net (code "10") (name "/CAP_VDDAR_MPU3") (class "Default")
      (node (ref "C164") (pin "1") (pinfunction "1_1") (pintype "passive"))
      (node (ref "U34") (pin "N15") (pinfunction "CAP_VDDAR_MPU3_N15") (pintype "power_in"))
    )
    (net (code "11") (name "/CAP_VDDAR_WKUP") (class "Default")
      (node (ref "C114") (pin "1") (pinfunction "1_1") (pintype "passive"))
      (node (ref "U34") (pin "Y10") (pinfunction "CAP_VDDAR_WKUP_Y10") (pintype "power_in"))
    )
    (net (code "12") (name "/CAP_VDDA_1P8_IOLDO1") (class "Default")
      (node (ref "C200") (pin "1") (pinfunction "1_1") (pintype "passive"))
      (node (ref "U34") (pin "Y19") (pinfunction "CAP_VDDA_1P8_IOLDO1_Y19") (pintype "power_in"))
    )
    (net (code "13") (name "CAP_VDDA_1P8_IOLDO0") (class "Default")
      (node (ref "C170") (pin "2") (pinfunction "2_2") (pintype "passive"))
      (node (ref "U34") (pin "G19") (pinfunction "CAP_VDDA_1P8_IOLDO0_G19") (pintype "power_in"))
    )
    (net (code "14") (name "CAP_VDDA_1P8_IOLDO_WKUP") (class "Default")
      (node (ref "C113") (pin "2") (pinfunction "2_2") (pintype "passive"))
      (node (ref "U34") (pin "AA8") (pinfunction "CAP_VDDA_1P8_IOLDO_WKUP_AA8") (pintype "power_in"))
    )
    (net (code "15") (name "CAP_VDDA_1P8_SDIO") (class "Default")
      (node (ref "C180") (pin "1") (pinfunction "1_1") (pintype "passive"))
      (node (ref "U34") (pin "J17") (pinfunction "CAP_VDDA_1P8_SDIO_J17") (pintype "power_in"))
    )
    (net (code "16") (name "CAP_VDDSHV_SDLDO") (class "Default")
      (node (ref "C541") (pin "1") (pinfunction "1_1") (pintype "passive"))
      (node (ref "U34") (pin "H18") (pinfunction "CAP_VDDSHV_SDLDO_H18") (pintype "power_in"))
    )
    (net (code "17") (name "CAP_VDD_WKUP") (class "Default")
      (node (ref "C115") (pin "1") (pinfunction "1_1") (pintype "passive"))
      (node (ref "U34") (pin "V9") (pinfunction "CAP_VDD_WKUP_V9") (pintype "power_in"))
    )
    (net (code "18") (name "DGND") (class "Default")
      (node (ref "C113") (pin "1") (pinfunction "1_1") (pintype "passive"))
      (node (ref "C114") (pin "2") (pinfunction "2_2") (pintype "passive"))
      (node (ref "C115") (pin "2") (pinfunction "2_2") (pintype "passive"))
      (node (ref "C116") (pin "2") (pinfunction "2_2") (pintype "passive"))
      (node (ref "C151") (pin "2") (pinfunction "2_2") (pintype "passive"))
      (node (ref "C157") (pin "2") (pinfunction "2_2") (pintype "passive"))
      (node (ref "C158") (pin "2") (pinfunction "2_2") (pintype "passive"))
      (node (ref "C159") (pin "2") (pinfunction "2_2") (pintype "passive"))
      (node (ref "C164") (pin "2") (pinfunction "2_2") (pintype "passive"))
      (node (ref "C165") (pin "2") (pinfunction "2_2") (pintype "passive"))
      (node (ref "C167") (pin "2") (pinfunction "2_2") (pintype "passive"))
      (node (ref "C170") (pin "1") (pinfunction "1_1") (pintype "passive"))
      (node (ref "C180") (pin "2") (pinfunction "2_2") (pintype "passive"))
      (node (ref "C200") (pin "2") (pinfunction "2_2") (pintype "passive"))
      (node (ref "C201") (pin "2") (pinfunction "2_2") (pintype "passive"))
      (node (ref "C373") (pin "2") (pinfunction "2_2") (pintype "passive"))
      (node (ref "C374") (pin "2") (pinfunction "2_2") (pintype "passive"))
      (node (ref "C375") (pin "2") (pinfunction "2_2") (pintype "passive"))
      (node (ref "C376") (pin "2") (pinfunction "2_2") (pintype "passive"))
      (node (ref "C377") (pin "2") (pinfunction "2_2") (pintype "passive"))
      (node (ref "C382") (pin "2") (pinfunction "2_2") (pintype "passive"))
      (node (ref "C383") (pin "2") (pinfunction "2_2") (pintype "passive"))
      (node (ref "C384") (pin "2") (pinfunction "2_2") (pintype "passive"))
      (node (ref "C386") (pin "2") (pinfunction "2_2") (pintype "passive"))
      (node (ref "C390") (pin "2") (pinfunction "2_2") (pintype "passive"))
      (node (ref "C391") (pin "2") (pinfunction "2_2") (pintype "passive"))
      (node (ref "C408") (pin "2") (pinfunction "2_2") (pintype "passive"))
      (node (ref "C409") (pin "2") (pinfunction "2_2") (pintype "passive"))
      (node (ref "C410") (pin "2") (pinfunction "2_2") (pintype "passive"))
      (node (ref "C420") (pin "2") (pinfunction "2_2") (pintype "passive"))
      (node (ref "C427") (pin "2") (pinfunction "2_2") (pintype "passive"))
      (node (ref "C428") (pin "2") (pinfunction "2_2") (pintype "passive"))
      (node (ref "C429") (pin "2") (pinfunction "2_2") (pintype "passive"))
      (node (ref "C431") (pin "2") (pinfunction "2_2") (pintype "passive"))
      (node (ref "C436") (pin "2") (pinfunction "2_2") (pintype "passive"))
      (node (ref "C437") (pin "2") (pinfunction "2_2") (pintype "passive"))
      (node (ref "C438") (pin "2") (pinfunction "2_2") (pintype "passive"))
      (node (ref "C441") (pin "2") (pinfunction "2_2") (pintype "passive"))
      (node (ref "C451") (pin "2") (pinfunction "2_2") (pintype "passive"))
      (node (ref "C452") (pin "2") (pinfunction "2_2") (pintype "passive"))
      (node (ref "C454") (pin "2") (pinfunction "2_2") (pintype "passive"))
      (node (ref "C456") (pin "2") (pinfunction "2_2") (pintype "passive"))
      (node (ref "C457") (pin "2") (pinfunction "2_2") (pintype "passive"))
      (node (ref "C458") (pin "2") (pinfunction "2_2") (pintype "passive"))
      (node (ref "C460") (pin "2") (pinfunction "2_2") (pintype "passive"))
      (node (ref "C461") (pin "2") (pinfunction "2_2") (pintype "passive"))
      (node (ref "C462") (pin "2") (pinfunction "2_2") (pintype "passive"))
      (node (ref "C463") (pin "2") (pinfunction "2_2") (pintype "passive"))
      (node (ref "C465") (pin "2") (pinfunction "2_2") (pintype "passive"))
      (node (ref "C467") (pin "2") (pinfunction "2_2") (pintype "passive"))
      (node (ref "C468") (pin "2") (pinfunction "2_2") (pintype "passive"))
      (node (ref "C469") (pin "2") (pinfunction "2_2") (pintype "passive"))
      (node (ref "C473") (pin "2") (pinfunction "2_2") (pintype "passive"))
      (node (ref "C476") (pin "2") (pinfunction "2_2") (pintype "passive"))
      (node (ref "C479") (pin "2") (pinfunction "2_2") (pintype "passive"))
      (node (ref "C482") (pin "2") (pinfunction "2_2") (pintype "passive"))
      (node (ref "C483") (pin "2") (pinfunction "2_2") (pintype "passive"))
      (node (ref "C484") (pin "2") (pinfunction "2_2") (pintype "passive"))
      (node (ref "C485") (pin "2") (pinfunction "2_2") (pintype "passive"))
      (node (ref "C486") (pin "2") (pinfunction "2_2") (pintype "passive"))
      (node (ref "C487") (pin "2") (pinfunction "2_2") (pintype "passive"))
      (node (ref "C488") (pin "2") (pinfunction "2_2") (pintype "passive"))
      (node (ref "C490") (pin "2") (pinfunction "2_2") (pintype "passive"))
      (node (ref "C491") (pin "2") (pinfunction "2_2") (pintype "passive"))
      (node (ref "C492") (pin "2") (pinfunction "2_2") (pintype "passive"))
      (node (ref "C493") (pin "2") (pinfunction "2_2") (pintype "passive"))
      (node (ref "C494") (pin "2") (pinfunction "2_2") (pintype "passive"))
      (node (ref "C496") (pin "2") (pinfunction "2_2") (pintype "passive"))
      (node (ref "C497") (pin "2") (pinfunction "2_2") (pintype "passive"))
      (node (ref "C498") (pin "2") (pinfunction "2_2") (pintype "passive"))
      (node (ref "C500") (pin "2") (pinfunction "2_2") (pintype "passive"))
      (node (ref "C502") (pin "2") (pinfunction "2_2") (pintype "passive"))
      (node (ref "C503") (pin "2") (pinfunction "2_2") (pintype "passive"))
      (node (ref "C509") (pin "2") (pinfunction "2_2") (pintype "passive"))
      (node (ref "C510") (pin "2") (pinfunction "2_2") (pintype "passive"))
      (node (ref "C511") (pin "2") (pinfunction "2_2") (pintype "passive"))
      (node (ref "C515") (pin "2") (pinfunction "2_2") (pintype "passive"))
      (node (ref "C516") (pin "2") (pinfunction "2_2") (pintype "passive"))
      (node (ref "C517") (pin "2") (pinfunction "2_2") (pintype "passive"))
      (node (ref "C518") (pin "2") (pinfunction "2_2") (pintype "passive"))
      (node (ref "C520") (pin "2") (pinfunction "2_2") (pintype "passive"))
      (node (ref "C524") (pin "2") (pinfunction "2_2") (pintype "passive"))
      (node (ref "C525") (pin "2") (pinfunction "2_2") (pintype "passive"))
      (node (ref "C526") (pin "2") (pinfunction "2_2") (pintype "passive"))
      (node (ref "C530") (pin "2") (pinfunction "2_2") (pintype "passive"))
      (node (ref "C531") (pin "2") (pinfunction "2_2") (pintype "passive"))
      (node (ref "C532") (pin "2") (pinfunction "2_2") (pintype "passive"))
      (node (ref "C533") (pin "2") (pinfunction "2_2") (pintype "passive"))
      (node (ref "C534") (pin "2") (pinfunction "2_2") (pintype "passive"))
      (node (ref "C535") (pin "2") (pinfunction "2_2") (pintype "passive"))
      (node (ref "C539") (pin "2") (pinfunction "2_2") (pintype "passive"))
      (node (ref "C541") (pin "2") (pinfunction "2_2") (pintype "passive"))
      (node (ref "C543") (pin "2") (pinfunction "2_2") (pintype "passive"))
      (node (ref "C550") (pin "2") (pinfunction "2_2") (pintype "passive"))
    )
    (net (code "19") (name "SoC_VDDS_DDR") (class "Default")
      (node (ref "C408") (pin "1") (pinfunction "1_1") (pintype "passive"))
      (node (ref "C409") (pin "1") (pinfunction "1_1") (pintype "passive"))
      (node (ref "C410") (pin "1") (pinfunction "1_1") (pintype "passive"))
      (node (ref "C420") (pin "1") (pinfunction "1_1") (pintype "passive"))
      (node (ref "C427") (pin "1") (pinfunction "1_1") (pintype "passive"))
      (node (ref "C428") (pin "1") (pinfunction "1_1") (pintype "passive"))
      (node (ref "C429") (pin "1") (pinfunction "1_1") (pintype "passive"))
      (node (ref "C436") (pin "1") (pinfunction "1_1") (pintype "passive"))
      (node (ref "C441") (pin "1") (pinfunction "1_1") (pintype "passive"))
      (node (ref "C454") (pin "1") (pinfunction "1_1") (pintype "passive"))
      (node (ref "C483") (pin "1") (pinfunction "1_1") (pintype "passive"))
      (node (ref "C493") (pin "1") (pinfunction "1_1") (pintype "passive"))
      (node (ref "U34") (pin "G10") (pinfunction "VDDS_DDR_G10") (pintype "power_in"))
      (node (ref "U34") (pin "G14") (pinfunction "VDDS_DDR_G14") (pintype "power_in"))
      (node (ref "U34") (pin "G8") (pinfunction "VDDS_DDR_G8") (pintype "power_in"))
      (node (ref "U34") (pin "H13") (pinfunction "VDDS_DDR_H13") (pintype "power_in"))
      (node (ref "U34") (pin "H7") (pinfunction "VDDS_DDR_H7") (pintype "power_in"))
      (node (ref "U34") (pin "H9") (pinfunction "VDDS_DDR_H9") (pintype "power_in"))
    )
    (net (code "20") (name "VDD_CORE") (class "Default")
      (node (ref "C373") (pin "1") (pinfunction "1_1") (pintype "passive"))
      (node (ref "C374") (pin "1") (pinfunction "1_1") (pintype "passive"))
      (node (ref "C376") (pin "1") (pinfunction "1_1") (pintype "passive"))
      (node (ref "C377") (pin "1") (pinfunction "1_1") (pintype "passive"))
      (node (ref "C382") (pin "1") (pinfunction "1_1") (pintype "passive"))
      (node (ref "C383") (pin "1") (pinfunction "1_1") (pintype "passive"))
      (node (ref "C390") (pin "1") (pinfunction "1_1") (pintype "passive"))
      (node (ref "C391") (pin "1") (pinfunction "1_1") (pintype "passive"))
      (node (ref "C431") (pin "1") (pinfunction "1_1") (pintype "passive"))
      (node (ref "C451") (pin "1") (pinfunction "1_1") (pintype "passive"))
      (node (ref "C469") (pin "1") (pinfunction "1_1") (pintype "passive"))
      (node (ref "C473") (pin "1") (pinfunction "1_1") (pintype "passive"))
      (node (ref "C476") (pin "1") (pinfunction "1_1") (pintype "passive"))
      (node (ref "C479") (pin "1") (pinfunction "1_1") (pintype "passive"))
      (node (ref "C484") (pin "1") (pinfunction "1_1") (pintype "passive"))
      (node (ref "C485") (pin "1") (pinfunction "1_1") (pintype "passive"))
      (node (ref "C486") (pin "1") (pinfunction "1_1") (pintype "passive"))
      (node (ref "C487") (pin "1") (pinfunction "1_1") (pintype "passive"))
      (node (ref "C488") (pin "1") (pinfunction "1_1") (pintype "passive"))
      (node (ref "C490") (pin "1") (pinfunction "1_1") (pintype "passive"))
      (node (ref "C491") (pin "1") (pinfunction "1_1") (pintype "passive"))
      (node (ref "C494") (pin "1") (pinfunction "1_1") (pintype "passive"))
      (node (ref "C500") (pin "1") (pinfunction "1_1") (pintype "passive"))
      (node (ref "C502") (pin "1") (pinfunction "1_1") (pintype "passive"))
      (node (ref "C503") (pin "1") (pinfunction "1_1") (pintype "passive"))
      (node (ref "C509") (pin "1") (pinfunction "1_1") (pintype "passive"))
      (node (ref "C510") (pin "1") (pinfunction "1_1") (pintype "passive"))
      (node (ref "C511") (pin "1") (pinfunction "1_1") (pintype "passive"))
      (node (ref "C516") (pin "1") (pinfunction "1_1") (pintype "passive"))
      (node (ref "C517") (pin "1") (pinfunction "1_1") (pintype "passive"))
      (node (ref "C518") (pin "1") (pinfunction "1_1") (pintype "passive"))
      (node (ref "C520") (pin "1") (pinfunction "1_1") (pintype "passive"))
      (node (ref "C531") (pin "1") (pinfunction "1_1") (pintype "passive"))
      (node (ref "C532") (pin "1") (pinfunction "1_1") (pintype "passive"))
      (node (ref "C533") (pin "1") (pinfunction "1_1") (pintype "passive"))
      (node (ref "C534") (pin "1") (pinfunction "1_1") (pintype "passive"))
      (node (ref "C539") (pin "1") (pinfunction "1_1") (pintype "passive"))
      (node (ref "C543") (pin "1") (pinfunction "1_1") (pintype "passive"))
      (node (ref "C550") (pin "1") (pinfunction "1_1") (pintype "passive"))
      (node (ref "U34") (pin "AA12") (pinfunction "VDD_AA12") (pintype "power_in"))
      (node (ref "U34") (pin "J10") (pinfunction "VDD_J10") (pintype "power_in"))
      (node (ref "U34") (pin "J12") (pinfunction "VDD_J12") (pintype "power_in"))
      (node (ref "U34") (pin "J14") (pinfunction "VDD_J14") (pintype "power_in"))
      (node (ref "U34") (pin "J19") (pinfunction "VDD_J19") (pintype "power_in"))
      (node (ref "U34") (pin "J8") (pinfunction "VDD_J8") (pintype "power_in"))
      (node (ref "U34") (pin "K13") (pinfunction "VDD_K13") (pintype "power_in"))
      (node (ref "U34") (pin "L14") (pinfunction "VDD_L14") (pintype "power_in"))
      (node (ref "U34") (pin "L19") (pinfunction "VDD_L19") (pintype "power_in"))
      (node (ref "U34") (pin "M13") (pinfunction "VDD_M13") (pintype "power_in"))
      (node (ref "U34") (pin "N14") (pinfunction "VDD_N14") (pintype "power_in"))
      (node (ref "U34") (pin "P13") (pinfunction "VDD_P13") (pintype "power_in"))
      (node (ref "U34") (pin "P15") (pinfunction "VDD_P15") (pintype "power_in"))
      (node (ref "U34") (pin "P19") (pinfunction "VDD_P19") (pintype "power_in"))
      (node (ref "U34") (pin "R14") (pinfunction "VDD_R14") (pintype "power_in"))
      (node (ref "U34") (pin "R16") (pinfunction "VDD_R16") (pintype "power_in"))
      (node (ref "U34") (pin "R18") (pinfunction "VDD_R18") (pintype "power_in"))
      (node (ref "U34") (pin "T13") (pinfunction "VDD_T13") (pintype "power_in"))
      (node (ref "U34") (pin "T15") (pinfunction "VDD_T15") (pintype "power_in"))
      (node (ref "U34") (pin "T17") (pinfunction "VDD_T17") (pintype "power_in"))
      (node (ref "U34") (pin "T19") (pinfunction "VDD_T19") (pintype "power_in"))
      (node (ref "U34") (pin "U14") (pinfunction "VDD_U14") (pintype "power_in"))
      (node (ref "U34") (pin "U16") (pinfunction "VDD_U16") (pintype "power_in"))
      (node (ref "U34") (pin "U18") (pinfunction "VDD_U18") (pintype "power_in"))
      (node (ref "U34") (pin "V13") (pinfunction "VDD_V13") (pintype "power_in"))
      (node (ref "U34") (pin "V15") (pinfunction "VDD_V15") (pintype "power_in"))
      (node (ref "U34") (pin "V19") (pinfunction "VDD_V19") (pintype "power_in"))
      (node (ref "U34") (pin "W14") (pinfunction "VDD_W14") (pintype "power_in"))
      (node (ref "U34") (pin "W18") (pinfunction "VDD_W18") (pintype "power_in"))
      (node (ref "U34") (pin "Y11") (pinfunction "VDD_Y11") (pintype "power_in"))
      (node (ref "U34") (pin "Y13") (pinfunction "VDD_Y13") (pintype "power_in"))
      (node (ref "U34") (pin "Y15") (pinfunction "VDD_Y15") (pintype "power_in"))
    )
    (net (code "21") (name "VDD_MCU") (class "Default")
      (node (ref "C375") (pin "1") (pinfunction "1_1") (pintype "passive"))
      (node (ref "C384") (pin "1") (pinfunction "1_1") (pintype "passive"))
      (node (ref "C452") (pin "1") (pinfunction "1_1") (pintype "passive"))
      (node (ref "C457") (pin "1") (pinfunction "1_1") (pintype "passive"))
      (node (ref "C458") (pin "1") (pinfunction "1_1") (pintype "passive"))
      (node (ref "C468") (pin "1") (pinfunction "1_1") (pintype "passive"))
      (node (ref "C482") (pin "1") (pinfunction "1_1") (pintype "passive"))
      (node (ref "U34") (pin "N10") (pinfunction "VDD_MCU_N10") (pintype "power_in"))
      (node (ref "U34") (pin "P11") (pinfunction "VDD_MCU_P11") (pintype "power_in"))
      (node (ref "U34") (pin "R10") (pinfunction "VDD_MCU_R10") (pintype "power_in"))
      (node (ref "U34") (pin "R12") (pinfunction "VDD_MCU_R12") (pintype "power_in"))
      (node (ref "U34") (pin "T11") (pinfunction "VDD_MCU_T11") (pintype "power_in"))
    )
    (net (code "22") (name "VDD_MPU") (class "Default")
      (node (ref "C437") (pin "1") (pinfunction "1_1") (pintype "passive"))
      (node (ref "C438") (pin "1") (pinfunction "1_1") (pintype "passive"))
      (node (ref "C456") (pin "1") (pinfunction "1_1") (pintype "passive"))
      (node (ref "C460") (pin "1") (pinfunction "1_1") (pintype "passive"))
      (node (ref "C461") (pin "1") (pinfunction "1_1") (pintype "passive"))
      (node (ref "C462") (pin "1") (pinfunction "1_1") (pintype "passive"))
      (node (ref "C463") (pin "1") (pinfunction "1_1") (pintype "passive"))
      (node (ref "C465") (pin "1") (pinfunction "1_1") (pintype "passive"))
      (node (ref "C467") (pin "1") (pinfunction "1_1") (pintype "passive"))
      (node (ref "C492") (pin "1") (pinfunction "1_1") (pintype "passive"))
      (node (ref "C496") (pin "1") (pinfunction "1_1") (pintype "passive"))
      (node (ref "C497") (pin "1") (pinfunction "1_1") (pintype "passive"))
      (node (ref "C498") (pin "1") (pinfunction "1_1") (pintype "passive"))
      (node (ref "C515") (pin "1") (pinfunction "1_1") (pintype "passive"))
      (node (ref "C524") (pin "1") (pinfunction "1_1") (pintype "passive"))
      (node (ref "C525") (pin "1") (pinfunction "1_1") (pintype "passive"))
      (node (ref "C526") (pin "1") (pinfunction "1_1") (pintype "passive"))
      (node (ref "C530") (pin "1") (pinfunction "1_1") (pintype "passive"))
      (node (ref "C535") (pin "1") (pinfunction "1_1") (pintype "passive"))
      (node (ref "U34") (pin "K11") (pinfunction "VDD_MPU0_K11") (pintype "power_in"))
      (node (ref "U34") (pin "K16") (pinfunction "VDD_MPU1_K16") (pintype "power_in"))
      (node (ref "U34") (pin "K18") (pinfunction "VDD_MPU1_K18") (pintype "power_in"))
      (node (ref "U34") (pin "K9") (pinfunction "VDD_MPU0_K9") (pintype "power_in"))
      (node (ref "U34") (pin "L10") (pinfunction "VDD_MPU0_L10") (pintype "power_in"))
      (node (ref "U34") (pin "L17") (pinfunction "VDD_MPU1_L17") (pintype "power_in"))
      (node (ref "U34") (pin "L8") (pinfunction "VDD_MPU0_L8") (pintype "power_in"))
      (node (ref "U34") (pin "M11") (pinfunction "VDD_MPU0_M11") (pintype "power_in"))
      (node (ref "U34") (pin "M16") (pinfunction "VDD_MPU1_M16") (pintype "power_in"))
      (node (ref "U34") (pin "M18") (pinfunction "VDD_MPU1_M18") (pintype "power_in"))
      (node (ref "U34") (pin "N17") (pinfunction "VDD_MPU1_N17") (pintype "power_in"))
    )
  )
)
